# SolBoutin.net
KiCad netlist of a schematic drawn in Altium Designer
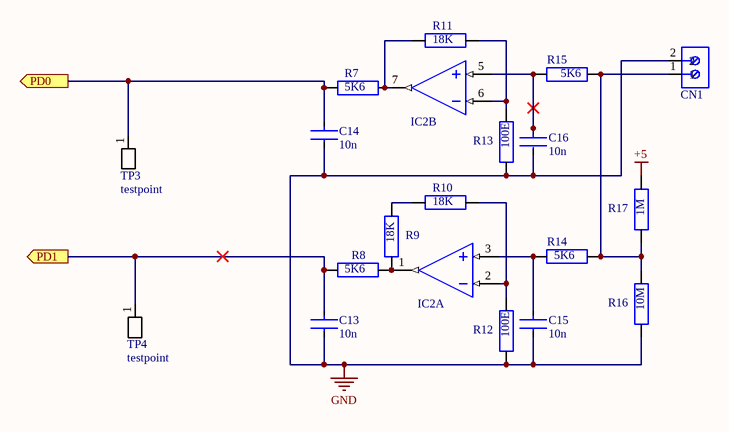
[diagram p0: SolBoutin.SchDoc]

(export (version "E")
  (design (tool "Eeschema 10.0.6"))
  (components
    (comp (ref "C13")
      (value "10n")
      (footprint "FP-C0805C-DN-IPC_A")
      (description "CAP CER 10000PF 200V X7R 0805")
      (fields
        (field (name "OCTOPART") "https://octopart.com/c0805c103k2ractu-kemet-9138347")
        (field (name "MANUFACTURER PART NUMBER") "C0805C103K2RACTU")
      )
      (libsource (lib "Altium Content Vault") (part "b4654b650e69147ec39a6b967a45e02"))
    )
    (comp (ref "C14")
      (value "10n")
      (footprint "FP-C0805C-DN-IPC_A")
      (description "CAP CER 10000PF 200V X7R 0805")
      (fields
        (field (name "OCTOPART") "https://octopart.com/c0805c103k2ractu-kemet-9138347")
        (field (name "MANUFACTURER PART NUMBER") "C0805C103K2RACTU")
      )
      (libsource (lib "Altium Content Vault") (part "b4654b650e69147ec39a6b967a45e02"))
    )
    (comp (ref "C15")
      (value "10n")
      (footprint "FP-C0805C-DN-IPC_A")
      (description "CAP CER 10000PF 200V X7R 0805")
      (fields
        (field (name "OCTOPART") "https://octopart.com/c0805c103k2ractu-kemet-9138347")
        (field (name "MANUFACTURER PART NUMBER") "C0805C103K2RACTU")
      )
      (libsource (lib "Altium Content Vault") (part "b4654b650e69147ec39a6b967a45e02"))
    )
    (comp (ref "C16")
      (value "10n")
      (footprint "FP-C0805C-DN-IPC_A")
      (description "CAP CER 10000PF 200V X7R 0805")
      (fields
        (field (name "OCTOPART") "https://octopart.com/c0805c103k2ractu-kemet-9138347")
        (field (name "MANUFACTURER PART NUMBER") "C0805C103K2RACTU")
      )
      (libsource (lib "Altium Content Vault") (part "b4654b650e69147ec39a6b967a45e02"))
    )
    (comp (ref "CN1")
      (value "282836-2")
      (footprint "cnn2pin")
      (description "Female Header, Pitch 5 mm, 1 x 2 Position, Height 10 mm, Tail Length 3.5 mm, Rohs, Bulk")
      (fields (field (name "VOLTAGE") "300V") (field (name "MANUFACTURER") "TE Connectivity"))
      (libsource (lib "soldeerstation") (part "CNN2P"))
    )
    (comp (ref "IC2")
      (value "MCP6002-E/P")
      (footprint "DIP8PIN")
      (description "None")
      (libsource (lib "soldeerstation") (part "AMP-OPA-MCP6002-IL8"))
    )
    (comp (ref "R7")
      (value "5K6")
      (footprint "res0805ph")
      (description "Resistor")
      (fields (field (name "MANUFACTURER_PART_NUMBER") "CPF0201D10K2C1"))
      (libsource (lib "") (part "Res_1"))
    )
    (comp (ref "R8")
      (value "5K6")
      (footprint "res0805ph")
      (description "Resistor")
      (fields (field (name "MANUFACTURER_PART_NUMBER") "CPF0201D10K2C1"))
      (libsource (lib "") (part "Res_1"))
    )
    (comp (ref "R9")
      (value "18K")
      (footprint "res0805ph")
      (description "Resistor")
      (fields (field (name "MANUFACTURER_PART_NUMBER") "CPF0201D10K2C1"))
      (libsource (lib "soldeerstation") (part "Res"))
    )
    (comp (ref "R10")
      (value "18K")
      (footprint "res0805ph")
      (description "Resistor")
      (fields (field (name "MANUFACTURER_PART_NUMBER") "CPF0201D10K2C1"))
      (libsource (lib "") (part "Res_1"))
    )
    (comp (ref "R11")
      (value "18K")
      (footprint "res0805ph")
      (description "Resistor")
      (fields (field (name "MANUFACTURER_PART_NUMBER") "CPF0201D10K2C1"))
      (libsource (lib "") (part "Res_1"))
    )
    (comp (ref "R12")
      (value "100E")
      (footprint "res0805ph")
      (description "Resistor")
      (fields (field (name "MANUFACTURER_PART_NUMBER") "CPF0201D10K2C1"))
      (libsource (lib "soldeerstation") (part "Res"))
    )
    (comp (ref "R13")
      (value "100E")
      (footprint "res0805ph")
      (description "Resistor")
      (fields (field (name "MANUFACTURER_PART_NUMBER") "CPF0201D10K2C1"))
      (libsource (lib "soldeerstation") (part "Res"))
    )
    (comp (ref "R14")
      (value "5K6")
      (footprint "res0805ph")
      (description "Resistor")
      (fields (field (name "MANUFACTURER_PART_NUMBER") "CPF0201D10K2C1"))
      (libsource (lib "") (part "Res_1"))
    )
    (comp (ref "R15")
      (value "5K6")
      (footprint "res0805ph")
      (description "Resistor")
      (fields (field (name "MANUFACTURER_PART_NUMBER") "CPF0201D10K2C1"))
      (libsource (lib "") (part "Res_1"))
    )
    (comp (ref "R16")
      (value "10M")
      (footprint "res0805ph")
      (description "Resistor")
      (fields (field (name "MANUFACTURER_PART_NUMBER") "CPF0201D10K2C1"))
      (libsource (lib "soldeerstation") (part "Res"))
    )
    (comp (ref "R17")
      (value "1M")
      (footprint "res0805ph")
      (description "Resistor")
      (fields (field (name "MANUFACTURER_PART_NUMBER") "CPF0201D10K2C1"))
      (libsource (lib "soldeerstation") (part "Res"))
    )
    (comp (ref "TP3")
      (value "testpoint")
      (footprint "testpin")
      (libsource (lib "soldeerstation") (part "testpoint"))
    )
    (comp (ref "TP4")
      (value "testpoint")
      (footprint "testpin")
      (libsource (lib "soldeerstation") (part "testpoint"))
    )
  )
  (nets
    (net (code "1") (name "+5") (class "Default")
      (node (ref "R17") (pin "2") (pinfunction "2_2") (pintype "passive"))
    )
    (net (code "2") (name "/PD0") (class "Default")
      (node (ref "C14") (pin "1") (pinfunction "1_1") (pintype "passive"))
      (node (ref "R7") (pin "2") (pinfunction "2_2") (pintype "passive"))
      (node (ref "TP3") (pin "1") (pinfunction "TP_1") (pintype "passive"))
    )
    (net (code "3") (name "/PD1") (class "Default")
      (node (ref "C13") (pin "1") (pinfunction "1_1") (pintype "passive"))
      (node (ref "R8") (pin "2") (pinfunction "2_2") (pintype "passive"))
      (node (ref "TP4") (pin "1") (pinfunction "TP_1") (pintype "passive"))
    )
    (net (code "4") (name "GND") (class "Default")
      (node (ref "C13") (pin "2") (pinfunction "2_2") (pintype "passive"))
      (node (ref "C14") (pin "2") (pinfunction "2_2") (pintype "passive"))
      (node (ref "C15") (pin "2") (pinfunction "2_2") (pintype "passive"))
      (node (ref "C16") (pin "2") (pinfunction "2_2") (pintype "passive"))
      (node (ref "CN1") (pin "2") (pinfunction "2_2") (pintype "passive"))
      (node (ref "R12") (pin "1") (pinfunction "1_1") (pintype "passive"))
      (node (ref "R13") (pin "1") (pinfunction "1_1") (pintype "passive"))
      (node (ref "R16") (pin "1") (pinfunction "1_1") (pintype "passive"))
    )
    (net (code "5") (name "Net-(CN1-Pad1)") (class "Default")
      (node (ref "CN1") (pin "1") (pinfunction "1_1") (pintype "passive"))
      (node (ref "R14") (pin "1") (pinfunction "1_1") (pintype "passive"))
      (node (ref "R15") (pin "1") (pinfunction "1_1") (pintype "passive"))
      (node (ref "R16") (pin "2") (pinfunction "2_2") (pintype "passive"))
      (node (ref "R17") (pin "1") (pinfunction "1_1") (pintype "passive"))
    )
    (net (code "6") (name "Net-(IC2A-VINA+)") (class "Default")
      (node (ref "C15") (pin "1") (pinfunction "1_1") (pintype "passive"))
      (node (ref "IC2") (pin "3") (pinfunction "VINA+_3") (pintype "input"))
      (node (ref "R14") (pin "2") (pinfunction "2_2") (pintype "passive"))
    )
    (net (code "7") (name "Net-(IC2A-VINA-)") (class "Default")
      (node (ref "IC2") (pin "2") (pinfunction "VINA-_2") (pintype "input"))
      (node (ref "R10") (pin "1") (pinfunction "1_1") (pintype "passive"))
      (node (ref "R12") (pin "2") (pinfunction "2_2") (pintype "passive"))
    )
    (net (code "8") (name "Net-(IC2A-VOUTA)") (class "Default")
      (node (ref "IC2") (pin "1") (pinfunction "VOUTA_1") (pintype "output"))
      (node (ref "R8") (pin "1") (pinfunction "1_1") (pintype "passive"))
      (node (ref "R9") (pin "1") (pinfunction "1_1") (pintype "passive"))
    )
    (net (code "9") (name "Net-(IC2B-VINB+)") (class "Default")
      (node (ref "C16") (pin "1") (pinfunction "1_1") (pintype "passive"))
      (node (ref "IC2") (pin "5") (pinfunction "VINB+_5") (pintype "input"))
      (node (ref "R15") (pin "2") (pinfunction "2_2") (pintype "passive"))
    )
    (net (code "10") (name "Net-(IC2B-VINB-)") (class "Default")
      (node (ref "IC2") (pin "6") (pinfunction "VINB-_6") (pintype "input"))
      (node (ref "R11") (pin "1") (pinfunction "1_1") (pintype "passive"))
      (node (ref "R13") (pin "2") (pinfunction "2_2") (pintype "passive"))
    )
    (net (code "11") (name "Net-(IC2B-VOUTB)") (class "Default")
      (node (ref "IC2") (pin "7") (pinfunction "VOUTB_7") (pintype "output"))
      (node (ref "R11") (pin "2") (pinfunction "2_2") (pintype "passive"))
      (node (ref "R7") (pin "1") (pinfunction "1_1") (pintype "passive"))
    )
    (net (code "12") (name "Net-(R10-Pad2)") (class "Default")
      (node (ref "R10") (pin "2") (pinfunction "2_2") (pintype "passive"))
      (node (ref "R9") (pin "2") (pinfunction "2_2") (pintype "passive"))
    )
  )
)
